# 5.net
KiCad netlist of a schematic drawn in Altium Designer
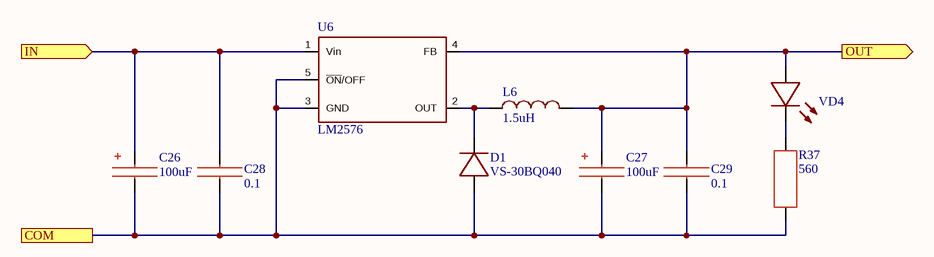
[diagram p0: 5.SchDoc]

(export (version "E")
  (design (tool "Eeschema 10.0.6"))
  (components
    (comp (ref "C26")
      (value "100uF")
      (footprint "TANTAL TYPE D")
      (libsource (lib "Capacitor") (part "Tantal D 100uF"))
    )
    (comp (ref "C27")
      (value "100uF")
      (footprint "TANTAL TYPE D")
      (libsource (lib "Capacitor") (part "Tantal D 100uF"))
    )
    (comp (ref "C28")
      (value "0.1")
      (footprint "Capacitor:CC0805_3D")
      (libsource (lib "Capacitor") (part "CC0805 X uF"))
    )
    (comp (ref "C29")
      (value "0.1")
      (footprint "Capacitor:CC0805_3D")
      (libsource (lib "Capacitor") (part "CC0805 X uF"))
    )
    (comp (ref "D1")
      (value "VS-30BQ040")
      (footprint "DO-214AB")
      (description "High Performance Schottky Rectifier, 3.0 A")
      (libsource (lib "VS-30BQ040") (part "VS-30BQ040"))
    )
    (comp (ref "L6") (value "4700uH") (footprint "SDR1105") (libsource (lib "SDR1105") (part "SDR1105")))
    (comp (ref "R37")
      (value "560")
      (footprint "Resistor:RC0805_3D")
      (libsource (lib "Resistor") (part "RC0805 X Ohm"))
    )
    (comp (ref "U6")
      (value "LM2576")
      (footprint "TO263-5")
      (description "SIMPLE SWITCHER® 3A Step-Down Voltage Regulator")
      (libsource (lib "LM2576") (part "LM2576"))
    )
    (comp (ref "VD4")
      (value "Value")
      (footprint "KA-3021SGCT:2030")
      (libsource (lib "KA-3021SGCT") (part "KA-3021SGCT"))
    )
  )
  (nets
    (net (code "1") (name "/COM") (class "Default")
      (node (ref "C26") (pin "1") (pinfunction "1_1") (pintype "passive"))
      (node (ref "C27") (pin "1") (pinfunction "1_1") (pintype "passive"))
      (node (ref "C28") (pin "1") (pinfunction "1_1") (pintype "passive"))
      (node (ref "C29") (pin "1") (pinfunction "1_1") (pintype "passive"))
      (node (ref "D1") (pin "2") (pinfunction "2_2") (pintype "passive"))
      (node (ref "R37") (pin "1") (pinfunction "1_1") (pintype "passive"))
      (node (ref "U6") (pin "3") (pinfunction "GND_3") (pintype "passive"))
      (node (ref "U6") (pin "5") (pinfunction "~{ON}/OFF_5") (pintype "passive"))
    )
    (net (code "2") (name "/IN") (class "Default")
      (node (ref "C26") (pin "2") (pinfunction "2_2") (pintype "passive"))
      (node (ref "C28") (pin "2") (pinfunction "2_2") (pintype "passive"))
      (node (ref "U6") (pin "1") (pinfunction "Vin_1") (pintype "passive"))
    )
    (net (code "3") (name "/OUT") (class "Default")
      (node (ref "C27") (pin "2") (pinfunction "2_2") (pintype "passive"))
      (node (ref "C29") (pin "2") (pinfunction "2_2") (pintype "passive"))
      (node (ref "L6") (pin "2") (pinfunction "2_2") (pintype "passive"))
      (node (ref "U6") (pin "4") (pinfunction "FB_4") (pintype "passive"))
      (node (ref "VD4") (pin "2") (pinfunction "2_2") (pintype "passive"))
    )
    (net (code "4") (name "Net-(R37-Pad2)") (class "Default")
      (node (ref "R37") (pin "2") (pinfunction "2_2") (pintype "passive"))
      (node (ref "VD4") (pin "1") (pinfunction "1_1") (pintype "passive"))
    )
    (net (code "5") (name "Net-(U6-OUT)") (class "Default")
      (node (ref "D1") (pin "1") (pinfunction "1_1") (pintype "passive"))
      (node (ref "L6") (pin "1") (pinfunction "1_1") (pintype "passive"))
      (node (ref "U6") (pin "2") (pinfunction "OUT_2") (pintype "passive"))
    )
  )
)
